# smr5.net
KiCad netlist of a schematic drawn in EAGLE
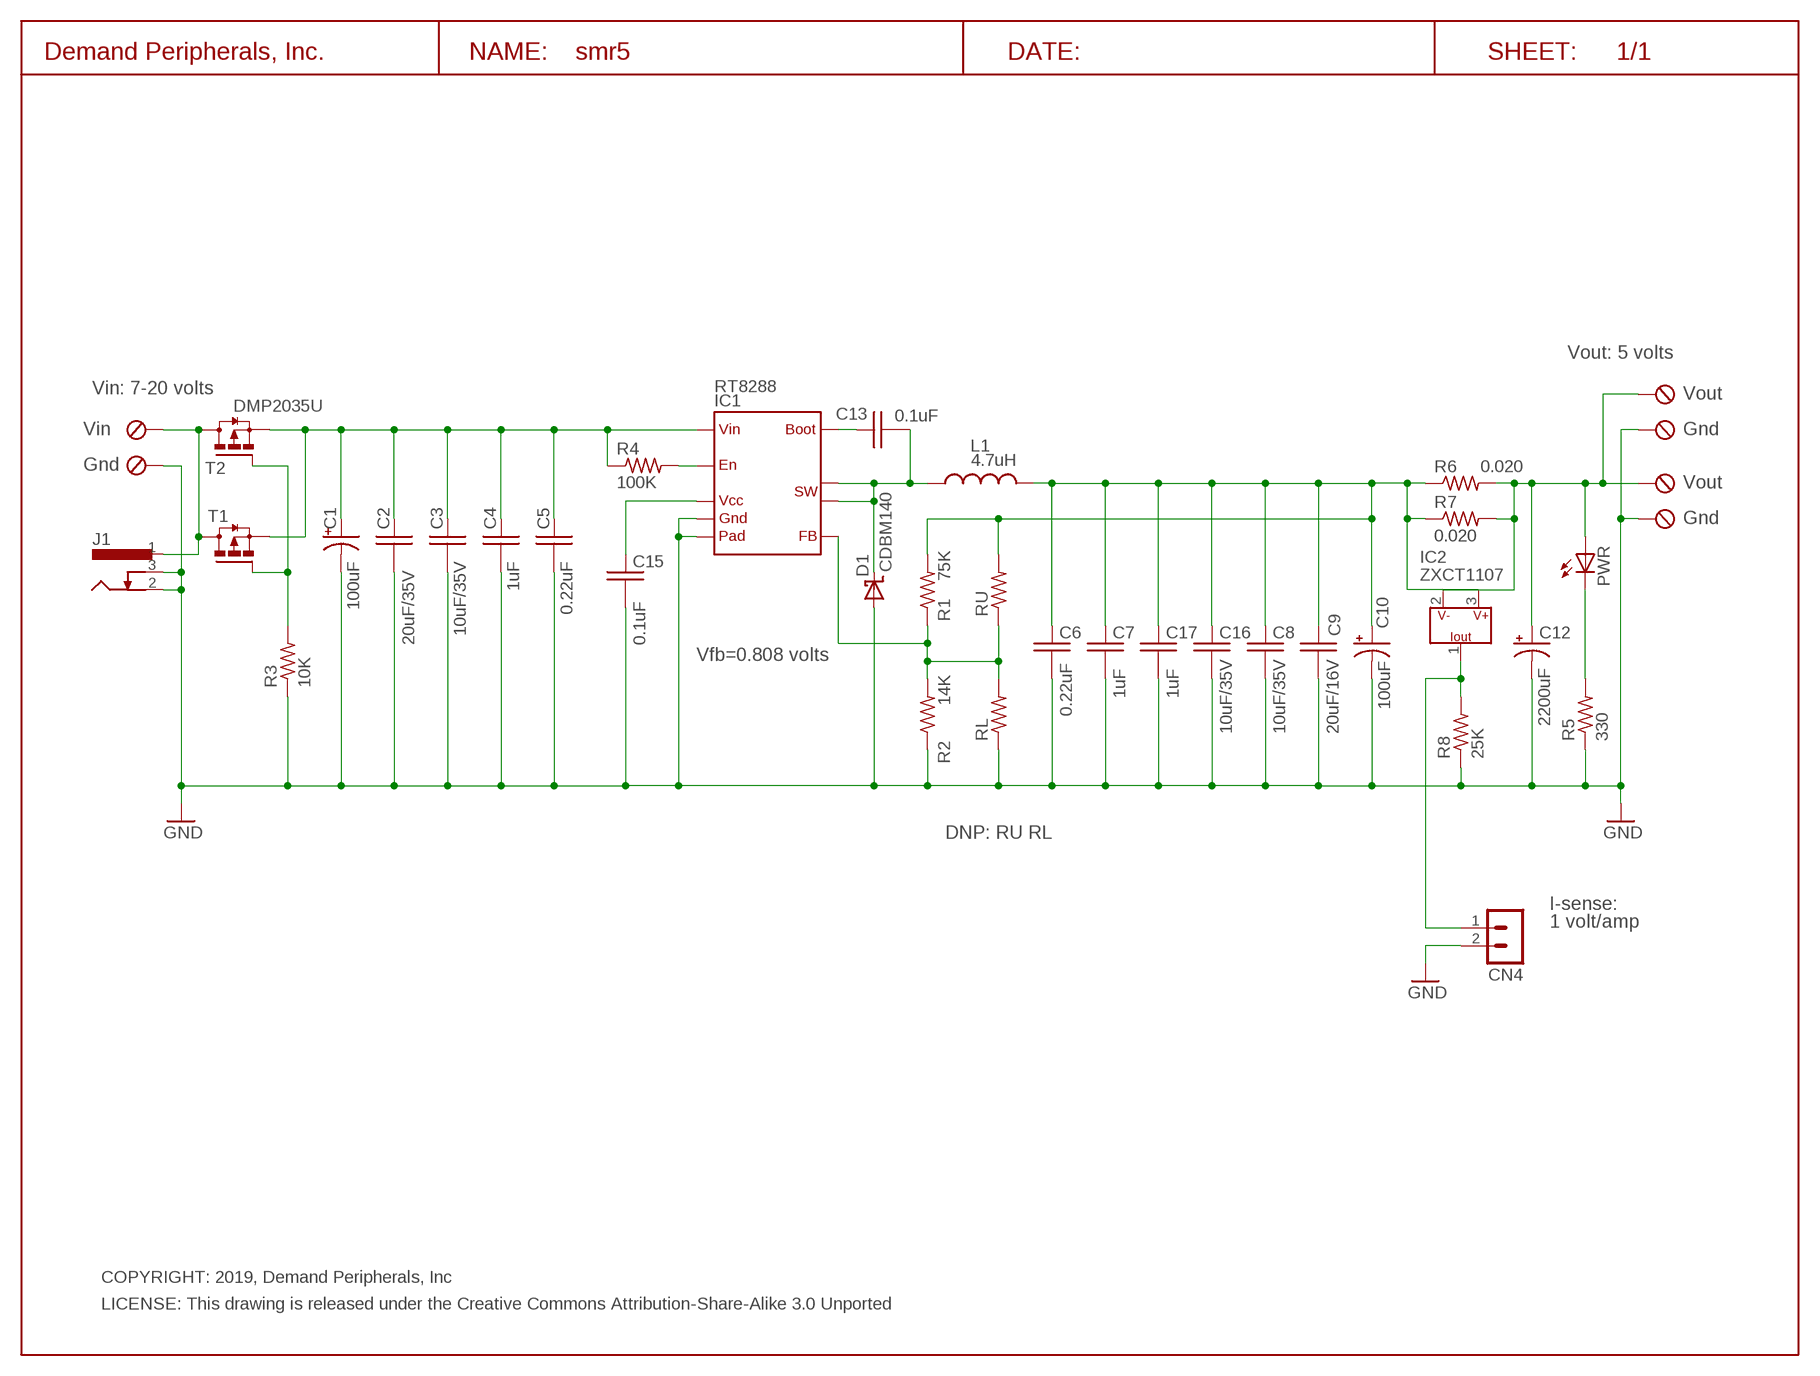
[diagram p0: schematic, sheet 1]

(export (version "E")
  (design (tool "Eeschema 10.0.6"))
  (components
    (comp (ref "C1")
      (value "100uF")
      (footprint "eagle-import:E3.5-8")
      (libsource (lib "eagle-import") (part "C100UF_E3.5-8"))
    )
    (comp (ref "C2")
      (value "20uF/35V")
      (footprint "eagle-import:C1206")
      (libsource (lib "eagle-import") (part "C22UF35V_"))
    )
    (comp (ref "C3")
      (value "10uF/35V")
      (footprint "eagle-import:C0805")
      (libsource (lib "eagle-import") (part "C10UF35V_C0805"))
    )
    (comp (ref "C4")
      (value "1uF")
      (footprint "eagle-import:C0603")
      (libsource (lib "eagle-import") (part "C1.0UF_C0603"))
    )
    (comp (ref "C5")
      (value "0.22uF")
      (footprint "eagle-import:C0805")
      (libsource (lib "eagle-import") (part "C0.22UFC0805"))
    )
    (comp (ref "C6")
      (value "0.22uF")
      (footprint "eagle-import:C0805")
      (libsource (lib "eagle-import") (part "C0.22UFC0805"))
    )
    (comp (ref "C7")
      (value "1uF")
      (footprint "eagle-import:C0603")
      (libsource (lib "eagle-import") (part "C1.0UF_C0603"))
    )
    (comp (ref "C8")
      (value "10uF/35V")
      (footprint "eagle-import:C0805")
      (libsource (lib "eagle-import") (part "C10UF35V_C0805"))
    )
    (comp (ref "C9")
      (value "20uF/16V")
      (footprint "eagle-import:C1210")
      (libsource (lib "eagle-import") (part "C22UF16V_"))
    )
    (comp (ref "C10")
      (value "100uF")
      (footprint "eagle-import:E3.5-8")
      (libsource (lib "eagle-import") (part "C100UF_E3.5-8"))
    )
    (comp (ref "C12")
      (value "2200uF")
      (footprint "eagle-import:E7,5-16")
      (libsource (lib "eagle-import") (part "C2200UF10V_E7,5-16"))
    )
    (comp (ref "C13")
      (value "0.1uF")
      (footprint "eagle-import:C0603")
      (libsource (lib "eagle-import") (part "C0.1UF_C0603"))
    )
    (comp (ref "C15")
      (value "0.1uF")
      (footprint "eagle-import:C0603")
      (libsource (lib "eagle-import") (part "C0.1UF_C0603"))
    )
    (comp (ref "C16")
      (value "10uF/35V")
      (footprint "eagle-import:C0805")
      (libsource (lib "eagle-import") (part "C10UF35V_C0805"))
    )
    (comp (ref "C17")
      (value "1uF")
      (footprint "eagle-import:C0603")
      (libsource (lib "eagle-import") (part "C1.0UF_C0603"))
    )
    (comp (ref "CN1")
      (value "TBLK-5.08-X2")
      (footprint "eagle-import:TBLK-5.08-X2")
      (libsource (lib "eagle-import") (part "TBLK-5.08-X2"))
    )
    (comp (ref "CN2")
      (value "TBLK-5.08-X2")
      (footprint "eagle-import:TBLK-5.08-X2")
      (libsource (lib "eagle-import") (part "TBLK-5.08-X2"))
    )
    (comp (ref "CN3")
      (value "TBLK-5.08-X2")
      (footprint "eagle-import:TBLK-5.08-X2")
      (libsource (lib "eagle-import") (part "TBLK-5.08-X2"))
    )
    (comp (ref "CN4")
      (value "HDR-2X1-LCK")
      (footprint "eagle-import:HDR-2X1")
      (libsource (lib "eagle-import") (part "HDR-2X1-LCK"))
    )
    (comp (ref "D1")
      (value "CDBM140")
      (footprint "eagle-import:SOD123T")
      (libsource (lib "eagle-import") (part "CDBM140"))
    )
    (comp (ref "IC1")
      (value "RT8288")
      (footprint "eagle-import:SOIC8-PAD")
      (libsource (lib "eagle-import") (part "RT8288"))
    )
    (comp (ref "IC2")
      (value "ZXCT1107")
      (footprint "eagle-import:ZXCT")
      (libsource (lib "eagle-import") (part "ZXCT1107"))
    )
    (comp (ref "J1")
      (value "DC-BARREL-JACK--55MM")
      (footprint "eagle-import:DC-BARREL-JACK-55MM")
      (libsource (lib "eagle-import") (part "DC-BARREL-JACK--55MM"))
    )
    (comp (ref "L1")
      (value "4.7uH")
      (footprint "eagle-import:TDKVLFIND")
      (libsource (lib "eagle-import") (part "VLF10045-4.7"))
    )
    (comp (ref "PWR")
      (value "LED-5MM-RED")
      (footprint "eagle-import:LED5MM")
      (libsource (lib "eagle-import") (part "LED-5MM-RED"))
    )
    (comp (ref "R1")
      (value "75K")
      (footprint "eagle-import:R0603")
      (libsource (lib "eagle-import") (part "R75K_R0603"))
    )
    (comp (ref "R2")
      (value "14K")
      (footprint "eagle-import:R0603")
      (libsource (lib "eagle-import") (part "R14K_R0603"))
    )
    (comp (ref "R3")
      (value "10K")
      (footprint "eagle-import:R0603")
      (libsource (lib "eagle-import") (part "R10K_R0603"))
    )
    (comp (ref "R4")
      (value "100K")
      (footprint "eagle-import:R0603")
      (libsource (lib "eagle-import") (part "R100K_R0603"))
    )
    (comp (ref "R5")
      (value "330")
      (footprint "eagle-import:R0603")
      (libsource (lib "eagle-import") (part "R330_R0603"))
    )
    (comp (ref "R6")
      (value "0.020")
      (footprint "eagle-import:R0805")
      (libsource (lib "eagle-import") (part "R0.02_R0805"))
    )
    (comp (ref "R7")
      (value "0.020")
      (footprint "eagle-import:R0805")
      (libsource (lib "eagle-import") (part "R0.02_R0805"))
    )
    (comp (ref "R8")
      (value "25K")
      (footprint "eagle-import:R0603")
      (libsource (lib "eagle-import") (part "R25K_R0603"))
    )
    (comp (ref "RL")
      (value "R0.02_R0805")
      (footprint "eagle-import:R0805")
      (libsource (lib "eagle-import") (part "R0.02_R0805"))
    )
    (comp (ref "RU")
      (value "R0.02_R0805")
      (footprint "eagle-import:R0805")
      (libsource (lib "eagle-import") (part "R0.02_R0805"))
    )
    (comp (ref "T1")
      (value "DMP2035U")
      (footprint "eagle-import:SOT23")
      (libsource (lib "eagle-import") (part "DMP2035"))
    )
    (comp (ref "T2")
      (value "DMP2035U")
      (footprint "eagle-import:SOT23")
      (libsource (lib "eagle-import") (part "DMP2035"))
    )
    (comp (ref "U$1")
      (value "DP_FRAME_L")
      (footprint "eagle-import:LETTER_L")
      (libsource (lib "eagle-import") (part "DP_FRAME_L"))
    )
  )
  (nets
    (net (code "1") (name "GND") (class "Default")
      (node (ref "C1") (pin "-") (pinfunction "-_-") (pintype "passive"))
      (node (ref "C10") (pin "-") (pinfunction "-_-") (pintype "passive"))
      (node (ref "C12") (pin "-") (pinfunction "-_-") (pintype "passive"))
      (node (ref "C15") (pin "2") (pinfunction "2_2") (pintype "passive"))
      (node (ref "C16") (pin "2") (pinfunction "2_2") (pintype "passive"))
      (node (ref "C17") (pin "2") (pinfunction "2_2") (pintype "passive"))
      (node (ref "C2") (pin "2") (pinfunction "2_2") (pintype "passive"))
      (node (ref "C3") (pin "2") (pinfunction "2_2") (pintype "passive"))
      (node (ref "C4") (pin "2") (pinfunction "2_2") (pintype "passive"))
      (node (ref "C5") (pin "2") (pinfunction "2_2") (pintype "passive"))
      (node (ref "C6") (pin "2") (pinfunction "2_2") (pintype "passive"))
      (node (ref "C7") (pin "2") (pinfunction "2_2") (pintype "passive"))
      (node (ref "C8") (pin "2") (pinfunction "2_2") (pintype "passive"))
      (node (ref "C9") (pin "2") (pinfunction "2_2") (pintype "passive"))
      (node (ref "CN1") (pin "1") (pinfunction "KL_1") (pintype "passive"))
      (node (ref "CN2") (pin "1") (pinfunction "KL_1") (pintype "passive"))
      (node (ref "CN3") (pin "1") (pinfunction "KL_1") (pintype "passive"))
      (node (ref "CN4") (pin "2") (pinfunction "1_2") (pintype "passive"))
      (node (ref "D1") (pin "A") (pinfunction "A_A") (pintype "passive"))
      (node (ref "IC1") (pin "8") (pinfunction "GND_8") (pintype "power_in"))
      (node (ref "IC1") (pin "9") (pinfunction "GND-PAD_9") (pintype "power_in"))
      (node (ref "J1") (pin "2") (pinfunction "2_2") (pintype "passive"))
      (node (ref "J1") (pin "3") (pinfunction "3_3") (pintype "passive"))
      (node (ref "R2") (pin "1") (pinfunction "1_1") (pintype "passive"))
      (node (ref "R3") (pin "1") (pinfunction "1_1") (pintype "passive"))
      (node (ref "R5") (pin "1") (pinfunction "1_1") (pintype "passive"))
      (node (ref "R8") (pin "1") (pinfunction "1_1") (pintype "passive"))
      (node (ref "RL") (pin "1") (pinfunction "1_1") (pintype "passive"))
    )
    (net (code "2") (name "Net-(CN1-KL1)") (class "Default")
      (node (ref "CN1") (pin "2") (pinfunction "KL1_2") (pintype "passive"))
      (node (ref "J1") (pin "1") (pinfunction "1_1") (pintype "passive"))
      (node (ref "T1") (pin "3") (pinfunction "D_3") (pintype "passive"))
      (node (ref "T2") (pin "3") (pinfunction "D_3") (pintype "passive"))
    )
    (net (code "3") (name "Net-(CN2-KL1)") (class "Default")
      (node (ref "C12") (pin "+") (pinfunction "+_+") (pintype "passive"))
      (node (ref "CN2") (pin "2") (pinfunction "KL1_2") (pintype "passive"))
      (node (ref "CN3") (pin "2") (pinfunction "KL1_2") (pintype "passive"))
      (node (ref "IC2") (pin "2") (pinfunction "V-_2") (pintype "bidirectional"))
      (node (ref "PWR") (pin "A") (pinfunction "A_A") (pintype "passive"))
      (node (ref "R6") (pin "2") (pinfunction "2_2") (pintype "passive"))
      (node (ref "R7") (pin "2") (pinfunction "2_2") (pintype "passive"))
    )
    (net (code "4") (name "Net-(CN4-2)") (class "Default")
      (node (ref "CN4") (pin "1") (pinfunction "2_1") (pintype "passive"))
      (node (ref "IC2") (pin "1") (pinfunction "IOUT_1") (pintype "bidirectional"))
      (node (ref "R8") (pin "2") (pinfunction "2_2") (pintype "passive"))
    )
    (net (code "5") (name "Net-(D1-CC)") (class "Default")
      (node (ref "C13") (pin "2") (pinfunction "2_2") (pintype "passive"))
      (node (ref "D1") (pin "C") (pinfunction "CC_C") (pintype "passive"))
      (node (ref "IC1") (pin "2") (pinfunction "SW0_2") (pintype "passive"))
      (node (ref "IC1") (pin "3") (pinfunction "SW1_3") (pintype "passive"))
      (node (ref "L1") (pin "P$1") (pinfunction "1_P$1") (pintype "passive"))
    )
    (net (code "6") (name "Net-(IC1-BOOT)") (class "Default")
      (node (ref "C13") (pin "1") (pinfunction "1_1") (pintype "passive"))
      (node (ref "IC1") (pin "4") (pinfunction "BOOT_4") (pintype "output"))
    )
    (net (code "7") (name "Net-(IC1-EN)") (class "Default")
      (node (ref "IC1") (pin "5") (pinfunction "EN_5") (pintype "bidirectional"))
      (node (ref "R4") (pin "2") (pinfunction "2_2") (pintype "passive"))
    )
    (net (code "8") (name "Net-(IC1-FB)") (class "Default")
      (node (ref "IC1") (pin "6") (pinfunction "FB_6") (pintype "input"))
      (node (ref "R1") (pin "1") (pinfunction "1_1") (pintype "passive"))
      (node (ref "R2") (pin "2") (pinfunction "2_2") (pintype "passive"))
      (node (ref "RL") (pin "2") (pinfunction "2_2") (pintype "passive"))
      (node (ref "RU") (pin "1") (pinfunction "1_1") (pintype "passive"))
    )
    (net (code "9") (name "Net-(IC1-VCC)") (class "Default")
      (node (ref "C15") (pin "1") (pinfunction "1_1") (pintype "passive"))
      (node (ref "IC1") (pin "7") (pinfunction "VCC_7") (pintype "power_in"))
    )
    (net (code "10") (name "Net-(IC1-VIN)") (class "Default")
      (node (ref "C1") (pin "+") (pinfunction "+_+") (pintype "passive"))
      (node (ref "C2") (pin "1") (pinfunction "1_1") (pintype "passive"))
      (node (ref "C3") (pin "1") (pinfunction "1_1") (pintype "passive"))
      (node (ref "C4") (pin "1") (pinfunction "1_1") (pintype "passive"))
      (node (ref "C5") (pin "1") (pinfunction "1_1") (pintype "passive"))
      (node (ref "IC1") (pin "1") (pinfunction "VIN_1") (pintype "bidirectional"))
      (node (ref "R4") (pin "1") (pinfunction "1_1") (pintype "passive"))
      (node (ref "T1") (pin "2") (pinfunction "S_2") (pintype "passive"))
      (node (ref "T2") (pin "2") (pinfunction "S_2") (pintype "passive"))
    )
    (net (code "11") (name "Net-(IC2-V+)") (class "Default")
      (node (ref "C10") (pin "+") (pinfunction "+_+") (pintype "passive"))
      (node (ref "C16") (pin "1") (pinfunction "1_1") (pintype "passive"))
      (node (ref "C17") (pin "1") (pinfunction "1_1") (pintype "passive"))
      (node (ref "C6") (pin "1") (pinfunction "1_1") (pintype "passive"))
      (node (ref "C7") (pin "1") (pinfunction "1_1") (pintype "passive"))
      (node (ref "C8") (pin "1") (pinfunction "1_1") (pintype "passive"))
      (node (ref "C9") (pin "1") (pinfunction "1_1") (pintype "passive"))
      (node (ref "IC2") (pin "3") (pinfunction "V+_3") (pintype "bidirectional"))
      (node (ref "L1") (pin "P$2") (pinfunction "2_P$2") (pintype "passive"))
      (node (ref "R1") (pin "2") (pinfunction "2_2") (pintype "passive"))
      (node (ref "R6") (pin "1") (pinfunction "1_1") (pintype "passive"))
      (node (ref "R7") (pin "1") (pinfunction "1_1") (pintype "passive"))
      (node (ref "RU") (pin "2") (pinfunction "2_2") (pintype "passive"))
    )
    (net (code "12") (name "Net-(PWR-PadC)") (class "Default")
      (node (ref "PWR") (pin "C") (pinfunction "C_C") (pintype "passive"))
      (node (ref "R5") (pin "2") (pinfunction "2_2") (pintype "passive"))
    )
    (net (code "13") (name "Net-(T1-G)") (class "Default")
      (node (ref "R3") (pin "2") (pinfunction "2_2") (pintype "passive"))
      (node (ref "T1") (pin "1") (pinfunction "G_1") (pintype "passive"))
      (node (ref "T2") (pin "1") (pinfunction "G_1") (pintype "passive"))
    )
  )
)
